# powermeter.net
KiCad netlist of a schematic drawn in EAGLE
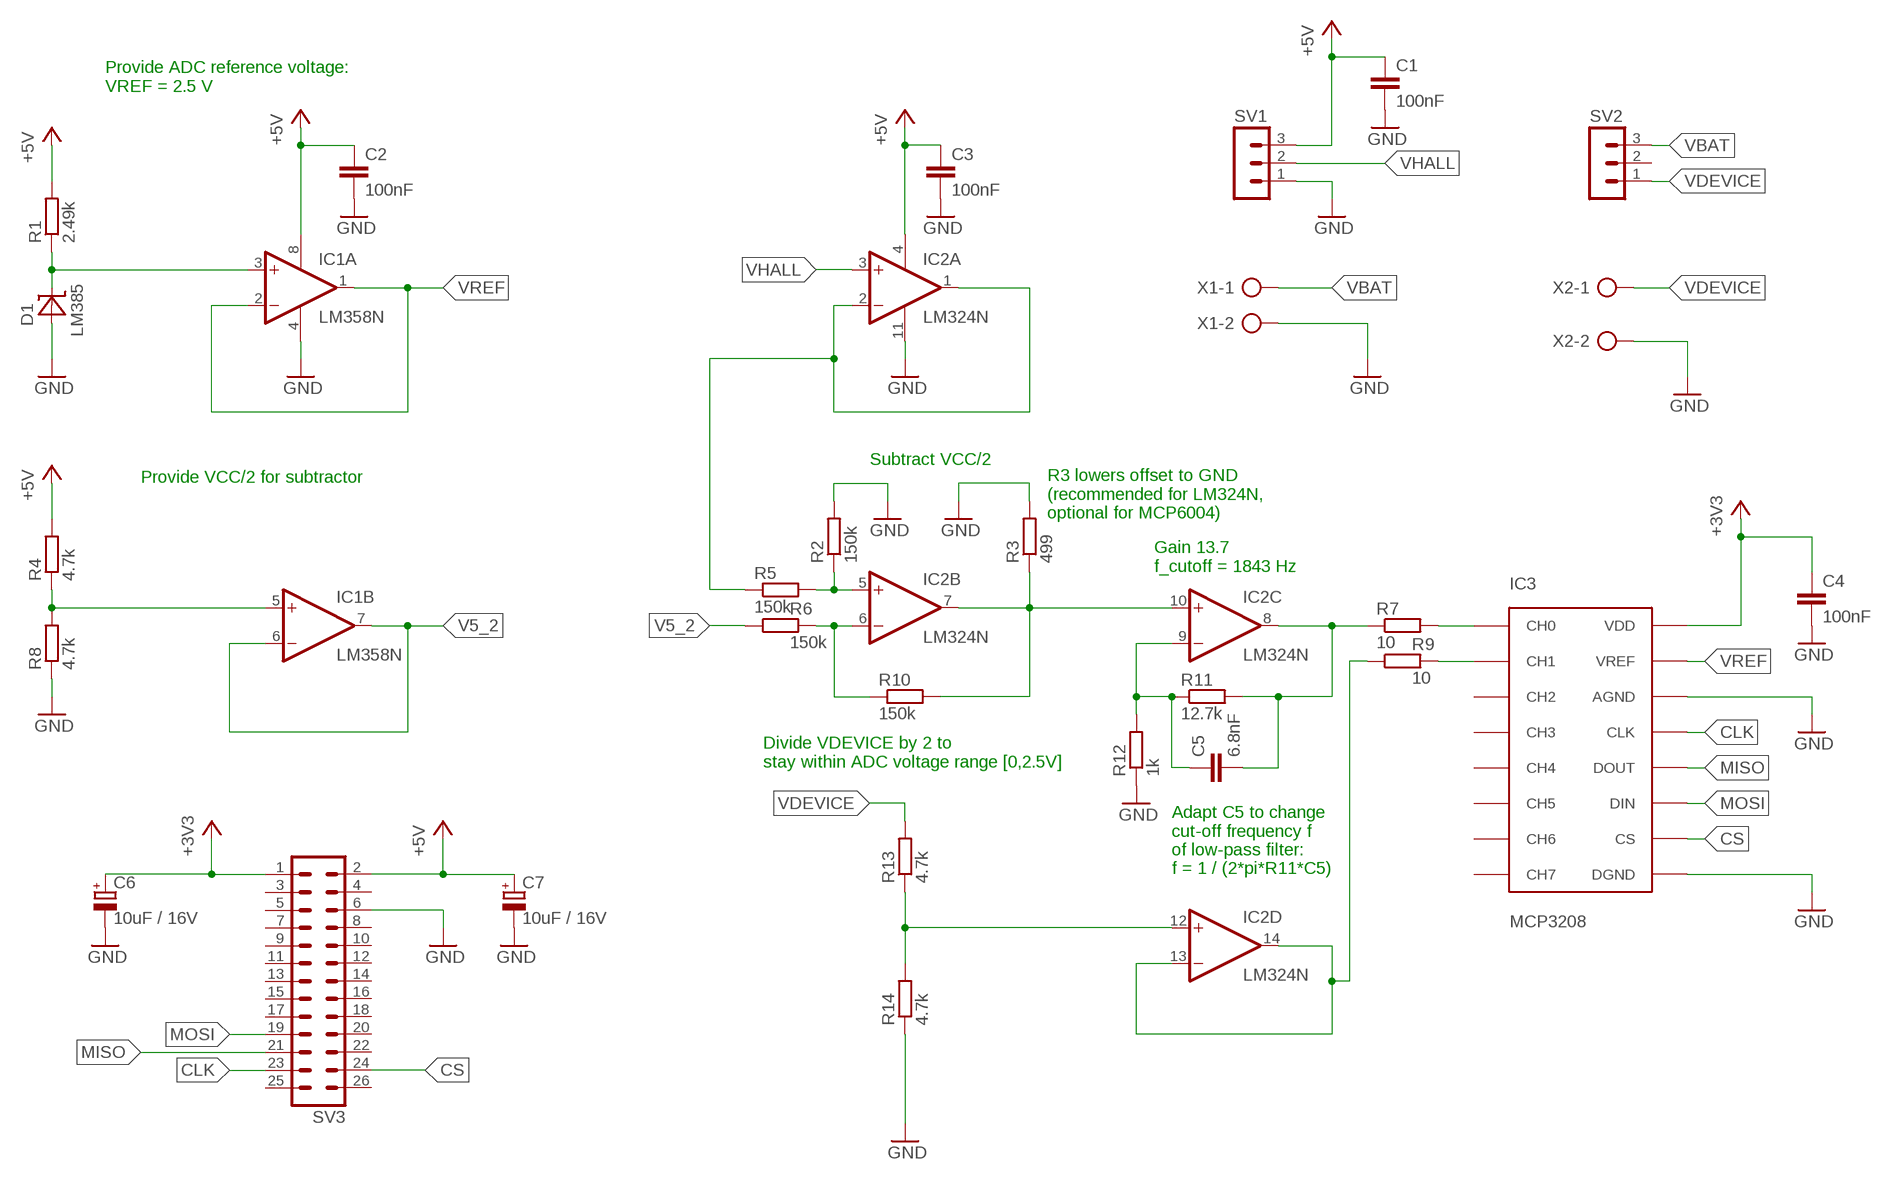
[diagram p0: schematic, sheet 1]

(export (version "E")
  (design (tool "Eeschema 10.0.6"))
  (components
    (comp (ref "C1")
      (value "100nF")
      (footprint "eagle-import:C050-024X044")
      (libsource (lib "eagle-import") (part "C-EU050-024X044"))
    )
    (comp (ref "C2")
      (value "100nF")
      (footprint "eagle-import:C050-024X044")
      (libsource (lib "eagle-import") (part "C-EU050-024X044"))
    )
    (comp (ref "C3")
      (value "100nF")
      (footprint "eagle-import:C050-024X044")
      (libsource (lib "eagle-import") (part "C-EU050-024X044"))
    )
    (comp (ref "C4")
      (value "100nF")
      (footprint "eagle-import:C050-024X044")
      (libsource (lib "eagle-import") (part "C-EU050-024X044"))
    )
    (comp (ref "C5")
      (value "6.8nF")
      (footprint "eagle-import:C050-030X075")
      (libsource (lib "eagle-import") (part "C-EU050-030X075"))
    )
    (comp (ref "C6")
      (value "10uF / 16V")
      (footprint "eagle-import:E2,5-5")
      (libsource (lib "eagle-import") (part "CPOL-EUE2.5-5"))
    )
    (comp (ref "C7")
      (value "10uF / 16V")
      (footprint "eagle-import:E2,5-5")
      (libsource (lib "eagle-import") (part "CPOL-EUE2.5-5"))
    )
    (comp (ref "D1")
      (value "LM385")
      (footprint "eagle-import:TO-92")
      (libsource (lib "eagle-import") (part "LM385"))
    )
    (comp (ref "IC1")
      (value "LM358N")
      (footprint "eagle-import:DIL08")
      (libsource (lib "eagle-import") (part "LM358N"))
    )
    (comp (ref "IC2")
      (value "LM324N")
      (footprint "eagle-import:DIL14")
      (libsource (lib "eagle-import") (part "LM324N"))
    )
    (comp (ref "IC3")
      (value "MCP3208")
      (footprint "eagle-import:DIL16")
      (libsource (lib "eagle-import") (part "MCP3208"))
    )
    (comp (ref "R1")
      (value "2.49k")
      (footprint "eagle-import:0207_7")
      (libsource (lib "eagle-import") (part "R-EU_0207/7"))
    )
    (comp (ref "R2")
      (value "150k")
      (footprint "eagle-import:0207_7")
      (libsource (lib "eagle-import") (part "R-EU_0207/7"))
    )
    (comp (ref "R3")
      (value "499")
      (footprint "eagle-import:0207_7")
      (libsource (lib "eagle-import") (part "R-EU_0207/7"))
    )
    (comp (ref "R4")
      (value "4.7k")
      (footprint "eagle-import:0207_7")
      (libsource (lib "eagle-import") (part "R-EU_0207/7"))
    )
    (comp (ref "R5")
      (value "150k")
      (footprint "eagle-import:0207_7")
      (libsource (lib "eagle-import") (part "R-EU_0207/7"))
    )
    (comp (ref "R6")
      (value "150k")
      (footprint "eagle-import:0207_7")
      (libsource (lib "eagle-import") (part "R-EU_0207/7"))
    )
    (comp (ref "R7")
      (value "10")
      (footprint "eagle-import:0207_7")
      (libsource (lib "eagle-import") (part "R-EU_0207/7"))
    )
    (comp (ref "R8")
      (value "4.7k")
      (footprint "eagle-import:0207_7")
      (libsource (lib "eagle-import") (part "R-EU_0207/7"))
    )
    (comp (ref "R9")
      (value "10")
      (footprint "eagle-import:0207_7")
      (libsource (lib "eagle-import") (part "R-EU_0207/7"))
    )
    (comp (ref "R10")
      (value "150k")
      (footprint "eagle-import:0207_7")
      (libsource (lib "eagle-import") (part "R-EU_0207/7"))
    )
    (comp (ref "R11")
      (value "12.7k")
      (footprint "eagle-import:0207_7")
      (libsource (lib "eagle-import") (part "R-EU_0207/7"))
    )
    (comp (ref "R12")
      (value "1k")
      (footprint "eagle-import:0207_7")
      (libsource (lib "eagle-import") (part "R-EU_0207/7"))
    )
    (comp (ref "R13")
      (value "4.7k")
      (footprint "eagle-import:0207_7")
      (libsource (lib "eagle-import") (part "R-EU_0207/7"))
    )
    (comp (ref "R14")
      (value "4.7k")
      (footprint "eagle-import:0207_7")
      (libsource (lib "eagle-import") (part "R-EU_0207/7"))
    )
    (comp (ref "SV1")
      (value "MA03-1")
      (footprint "eagle-import:MA03-1")
      (libsource (lib "eagle-import") (part "MA03-1"))
    )
    (comp (ref "SV2")
      (value "MA03-1")
      (footprint "eagle-import:MA03-1")
      (libsource (lib "eagle-import") (part "MA03-1"))
    )
    (comp (ref "SV3")
      (value "ML26")
      (footprint "eagle-import:ML26")
      (libsource (lib "eagle-import") (part "ML26"))
    )
    (comp (ref "X1")
      (value "AK500/2")
      (footprint "eagle-import:AK500_2")
      (libsource (lib "eagle-import") (part "AK500/2"))
    )
    (comp (ref "X2")
      (value "AK500/2")
      (footprint "eagle-import:AK500_2")
      (libsource (lib "eagle-import") (part "AK500/2"))
    )
  )
  (nets
    (net (code "1") (name "+3V3") (class "Default")
      (node (ref "C4") (pin "1") (pinfunction "1_1") (pintype "passive"))
      (node (ref "C6") (pin "+") (pinfunction "+_+") (pintype "passive"))
      (node (ref "IC3") (pin "VDD") (pinfunction "VDD_VDD") (pintype "power_in"))
      (node (ref "SV3") (pin "1") (pinfunction "1_1") (pintype "passive"))
    )
    (net (code "2") (name "+5V") (class "Default")
      (node (ref "C1") (pin "1") (pinfunction "1_1") (pintype "passive"))
      (node (ref "C2") (pin "1") (pinfunction "1_1") (pintype "passive"))
      (node (ref "C3") (pin "1") (pinfunction "1_1") (pintype "passive"))
      (node (ref "C7") (pin "+") (pinfunction "+_+") (pintype "passive"))
      (node (ref "IC1") (pin "8") (pinfunction "V+_8") (pintype "power_in"))
      (node (ref "IC2") (pin "4") (pinfunction "V+_4") (pintype "power_in"))
      (node (ref "R1") (pin "2") (pinfunction "2_2") (pintype "passive"))
      (node (ref "R4") (pin "2") (pinfunction "2_2") (pintype "passive"))
      (node (ref "SV1") (pin "3") (pinfunction "3_3") (pintype "passive"))
      (node (ref "SV3") (pin "2") (pinfunction "2_2") (pintype "passive"))
    )
    (net (code "3") (name "CLK") (class "Default")
      (node (ref "IC3") (pin "CLK") (pinfunction "CLK_CLK") (pintype "input"))
      (node (ref "SV3") (pin "23") (pinfunction "23_23") (pintype "passive"))
    )
    (net (code "4") (name "CS") (class "Default")
      (node (ref "IC3") (pin "CS") (pinfunction "CS_CS") (pintype "input"))
      (node (ref "SV3") (pin "24") (pinfunction "24_24") (pintype "passive"))
    )
    (net (code "5") (name "GND") (class "Default")
      (node (ref "C1") (pin "2") (pinfunction "2_2") (pintype "passive"))
      (node (ref "C2") (pin "2") (pinfunction "2_2") (pintype "passive"))
      (node (ref "C3") (pin "2") (pinfunction "2_2") (pintype "passive"))
      (node (ref "C4") (pin "2") (pinfunction "2_2") (pintype "passive"))
      (node (ref "C6") (pin "-") (pinfunction "-_-") (pintype "passive"))
      (node (ref "C7") (pin "-") (pinfunction "-_-") (pintype "passive"))
      (node (ref "D1") (pin "+") (pinfunction "+_+") (pintype "passive"))
      (node (ref "IC1") (pin "4") (pinfunction "V-_4") (pintype "power_in"))
      (node (ref "IC2") (pin "11") (pinfunction "V-_11") (pintype "power_in"))
      (node (ref "IC3") (pin "AGND") (pinfunction "AGND_AGND") (pintype "power_in"))
      (node (ref "IC3") (pin "DGND") (pinfunction "DGND_DGND") (pintype "power_in"))
      (node (ref "R12") (pin "1") (pinfunction "1_1") (pintype "passive"))
      (node (ref "R14") (pin "1") (pinfunction "1_1") (pintype "passive"))
      (node (ref "R2") (pin "2") (pinfunction "2_2") (pintype "passive"))
      (node (ref "R3") (pin "2") (pinfunction "2_2") (pintype "passive"))
      (node (ref "R8") (pin "1") (pinfunction "1_1") (pintype "passive"))
      (node (ref "SV1") (pin "1") (pinfunction "1_1") (pintype "passive"))
      (node (ref "SV3") (pin "6") (pinfunction "6_6") (pintype "passive"))
      (node (ref "X1") (pin "2") (pinfunction "KL_2") (pintype "passive"))
      (node (ref "X2") (pin "2") (pinfunction "KL_2") (pintype "passive"))
    )
    (net (code "6") (name "MISO") (class "Default")
      (node (ref "IC3") (pin "DOUT") (pinfunction "DOUT_DOUT") (pintype "output"))
      (node (ref "SV3") (pin "21") (pinfunction "21_21") (pintype "passive"))
    )
    (net (code "7") (name "MOSI") (class "Default")
      (node (ref "IC3") (pin "DIN") (pinfunction "DIN_DIN") (pintype "input"))
      (node (ref "SV3") (pin "19") (pinfunction "19_19") (pintype "passive"))
    )
    (net (code "8") (name "Net-(IC1A-+IN)") (class "Default")
      (node (ref "D1") (pin "-") (pinfunction "-_-") (pintype "passive"))
      (node (ref "IC1") (pin "3") (pinfunction "+IN_3") (pintype "input"))
      (node (ref "R1") (pin "1") (pinfunction "1_1") (pintype "passive"))
    )
    (net (code "9") (name "Net-(IC1B-+IN)") (class "Default")
      (node (ref "IC1") (pin "5") (pinfunction "+IN_5") (pintype "input"))
      (node (ref "R4") (pin "1") (pinfunction "1_1") (pintype "passive"))
      (node (ref "R8") (pin "2") (pinfunction "2_2") (pintype "passive"))
    )
    (net (code "10") (name "Net-(IC2A--IN)") (class "Default")
      (node (ref "IC2") (pin "1") (pinfunction "OUT_1") (pintype "output"))
      (node (ref "IC2") (pin "2") (pinfunction "-IN_2") (pintype "input"))
      (node (ref "R5") (pin "1") (pinfunction "1_1") (pintype "passive"))
    )
    (net (code "11") (name "Net-(IC2B-+IN)") (class "Default")
      (node (ref "IC2") (pin "5") (pinfunction "+IN_5") (pintype "input"))
      (node (ref "R2") (pin "1") (pinfunction "1_1") (pintype "passive"))
      (node (ref "R5") (pin "2") (pinfunction "2_2") (pintype "passive"))
    )
    (net (code "12") (name "Net-(IC2B--IN)") (class "Default")
      (node (ref "IC2") (pin "6") (pinfunction "-IN_6") (pintype "input"))
      (node (ref "R10") (pin "1") (pinfunction "1_1") (pintype "passive"))
      (node (ref "R6") (pin "2") (pinfunction "2_2") (pintype "passive"))
    )
    (net (code "13") (name "Net-(IC2B-OUT)") (class "Default")
      (node (ref "IC2") (pin "10") (pinfunction "+IN_10") (pintype "input"))
      (node (ref "IC2") (pin "7") (pinfunction "OUT_7") (pintype "output"))
      (node (ref "R10") (pin "2") (pinfunction "2_2") (pintype "passive"))
      (node (ref "R3") (pin "1") (pinfunction "1_1") (pintype "passive"))
    )
    (net (code "14") (name "Net-(IC2C--IN)") (class "Default")
      (node (ref "C5") (pin "1") (pinfunction "1_1") (pintype "passive"))
      (node (ref "IC2") (pin "9") (pinfunction "-IN_9") (pintype "input"))
      (node (ref "R11") (pin "1") (pinfunction "1_1") (pintype "passive"))
      (node (ref "R12") (pin "2") (pinfunction "2_2") (pintype "passive"))
    )
    (net (code "15") (name "Net-(IC2C-OUT)") (class "Default")
      (node (ref "C5") (pin "2") (pinfunction "2_2") (pintype "passive"))
      (node (ref "IC2") (pin "8") (pinfunction "OUT_8") (pintype "output"))
      (node (ref "R11") (pin "2") (pinfunction "2_2") (pintype "passive"))
      (node (ref "R7") (pin "1") (pinfunction "1_1") (pintype "passive"))
    )
    (net (code "16") (name "Net-(IC2D-+IN)") (class "Default")
      (node (ref "IC2") (pin "12") (pinfunction "+IN_12") (pintype "input"))
      (node (ref "R13") (pin "1") (pinfunction "1_1") (pintype "passive"))
      (node (ref "R14") (pin "2") (pinfunction "2_2") (pintype "passive"))
    )
    (net (code "17") (name "Net-(IC2D--IN)") (class "Default")
      (node (ref "IC2") (pin "13") (pinfunction "-IN_13") (pintype "input"))
      (node (ref "IC2") (pin "14") (pinfunction "OUT_14") (pintype "output"))
      (node (ref "R9") (pin "1") (pinfunction "1_1") (pintype "passive"))
    )
    (net (code "18") (name "Net-(IC3-PadCH0)") (class "Default")
      (node (ref "IC3") (pin "CH0") (pinfunction "CH0_CH0") (pintype "input"))
      (node (ref "R7") (pin "2") (pinfunction "2_2") (pintype "passive"))
    )
    (net (code "19") (name "Net-(IC3-PadCH1)") (class "Default")
      (node (ref "IC3") (pin "CH1") (pinfunction "CH1_CH1") (pintype "input"))
      (node (ref "R9") (pin "2") (pinfunction "2_2") (pintype "passive"))
    )
    (net (code "20") (name "V5_2") (class "Default")
      (node (ref "IC1") (pin "6") (pinfunction "-IN_6") (pintype "input"))
      (node (ref "IC1") (pin "7") (pinfunction "OUT_7") (pintype "output"))
      (node (ref "R6") (pin "1") (pinfunction "1_1") (pintype "passive"))
    )
    (net (code "21") (name "VBAT") (class "Default")
      (node (ref "SV2") (pin "3") (pinfunction "3_3") (pintype "passive"))
      (node (ref "X1") (pin "1") (pinfunction "KL_1") (pintype "passive"))
    )
    (net (code "22") (name "VDEVICE") (class "Default")
      (node (ref "R13") (pin "2") (pinfunction "2_2") (pintype "passive"))
      (node (ref "SV2") (pin "1") (pinfunction "1_1") (pintype "passive"))
      (node (ref "X2") (pin "1") (pinfunction "KL_1") (pintype "passive"))
    )
    (net (code "23") (name "VHALL") (class "Default")
      (node (ref "IC2") (pin "3") (pinfunction "+IN_3") (pintype "input"))
      (node (ref "SV1") (pin "2") (pinfunction "2_2") (pintype "passive"))
    )
    (net (code "24") (name "VREF") (class "Default")
      (node (ref "IC1") (pin "1") (pinfunction "OUT_1") (pintype "output"))
      (node (ref "IC1") (pin "2") (pinfunction "-IN_2") (pintype "input"))
      (node (ref "IC3") (pin "VREF") (pinfunction "VREF_VREF") (pintype "input"))
    )
    (net (code "25") (name "unconnected-(IC3-PadCH2)") (class "Default")
      (node (ref "IC3") (pin "CH2") (pinfunction "CH2_CH2") (pintype "input"))
    )
    (net (code "26") (name "unconnected-(IC3-PadCH3)") (class "Default")
      (node (ref "IC3") (pin "CH3") (pinfunction "CH3_CH3") (pintype "input"))
    )
    (net (code "27") (name "unconnected-(IC3-PadCH4)") (class "Default")
      (node (ref "IC3") (pin "CH4") (pinfunction "CH4_CH4") (pintype "input"))
    )
    (net (code "28") (name "unconnected-(IC3-PadCH5)") (class "Default")
      (node (ref "IC3") (pin "CH5") (pinfunction "CH5_CH5") (pintype "input"))
    )
    (net (code "29") (name "unconnected-(IC3-PadCH6)") (class "Default")
      (node (ref "IC3") (pin "CH6") (pinfunction "CH6_CH6") (pintype "input"))
    )
    (net (code "30") (name "unconnected-(IC3-PadCH7)") (class "Default")
      (node (ref "IC3") (pin "CH7") (pinfunction "CH7_CH7") (pintype "input"))
    )
    (net (code "31") (name "unconnected-(SV2-Pad2)") (class "Default")
      (node (ref "SV2") (pin "2") (pinfunction "2_2") (pintype "passive"))
    )
    (net (code "32") (name "unconnected-(SV3-Pad3)") (class "Default")
      (node (ref "SV3") (pin "3") (pinfunction "3_3") (pintype "passive"))
    )
    (net (code "33") (name "unconnected-(SV3-Pad4)") (class "Default")
      (node (ref "SV3") (pin "4") (pinfunction "4_4") (pintype "passive"))
    )
    (net (code "34") (name "unconnected-(SV3-Pad5)") (class "Default")
      (node (ref "SV3") (pin "5") (pinfunction "5_5") (pintype "passive"))
    )
    (net (code "35") (name "unconnected-(SV3-Pad7)") (class "Default")
      (node (ref "SV3") (pin "7") (pinfunction "7_7") (pintype "passive"))
    )
    (net (code "36") (name "unconnected-(SV3-Pad8)") (class "Default")
      (node (ref "SV3") (pin "8") (pinfunction "8_8") (pintype "passive"))
    )
    (net (code "37") (name "unconnected-(SV3-Pad9)") (class "Default")
      (node (ref "SV3") (pin "9") (pinfunction "9_9") (pintype "passive"))
    )
    (net (code "38") (name "unconnected-(SV3-Pad10)") (class "Default")
      (node (ref "SV3") (pin "10") (pinfunction "10_10") (pintype "passive"))
    )
    (net (code "39") (name "unconnected-(SV3-Pad11)") (class "Default")
      (node (ref "SV3") (pin "11") (pinfunction "11_11") (pintype "passive"))
    )
    (net (code "40") (name "unconnected-(SV3-Pad12)") (class "Default")
      (node (ref "SV3") (pin "12") (pinfunction "12_12") (pintype "passive"))
    )
    (net (code "41") (name "unconnected-(SV3-Pad13)") (class "Default")
      (node (ref "SV3") (pin "13") (pinfunction "13_13") (pintype "passive"))
    )
    (net (code "42") (name "unconnected-(SV3-Pad14)") (class "Default")
      (node (ref "SV3") (pin "14") (pinfunction "14_14") (pintype "passive"))
    )
    (net (code "43") (name "unconnected-(SV3-Pad15)") (class "Default")
      (node (ref "SV3") (pin "15") (pinfunction "15_15") (pintype "passive"))
    )
    (net (code "44") (name "unconnected-(SV3-Pad16)") (class "Default")
      (node (ref "SV3") (pin "16") (pinfunction "16_16") (pintype "passive"))
    )
    (net (code "45") (name "unconnected-(SV3-Pad17)") (class "Default")
      (node (ref "SV3") (pin "17") (pinfunction "17_17") (pintype "passive"))
    )
    (net (code "46") (name "unconnected-(SV3-Pad18)") (class "Default")
      (node (ref "SV3") (pin "18") (pinfunction "18_18") (pintype "passive"))
    )
    (net (code "47") (name "unconnected-(SV3-Pad20)") (class "Default")
      (node (ref "SV3") (pin "20") (pinfunction "20_20") (pintype "passive"))
    )
    (net (code "48") (name "unconnected-(SV3-Pad22)") (class "Default")
      (node (ref "SV3") (pin "22") (pinfunction "22_22") (pintype "passive"))
    )
    (net (code "49") (name "unconnected-(SV3-Pad25)") (class "Default")
      (node (ref "SV3") (pin "25") (pinfunction "25_25") (pintype "passive"))
    )
    (net (code "50") (name "unconnected-(SV3-Pad26)") (class "Default")
      (node (ref "SV3") (pin "26") (pinfunction "26_26") (pintype "passive"))
    )
  )
)
